# LB_BIT_i13_LIGHTSENSOR-v02_rev1.net
KiCad netlist of a schematic drawn in EAGLE
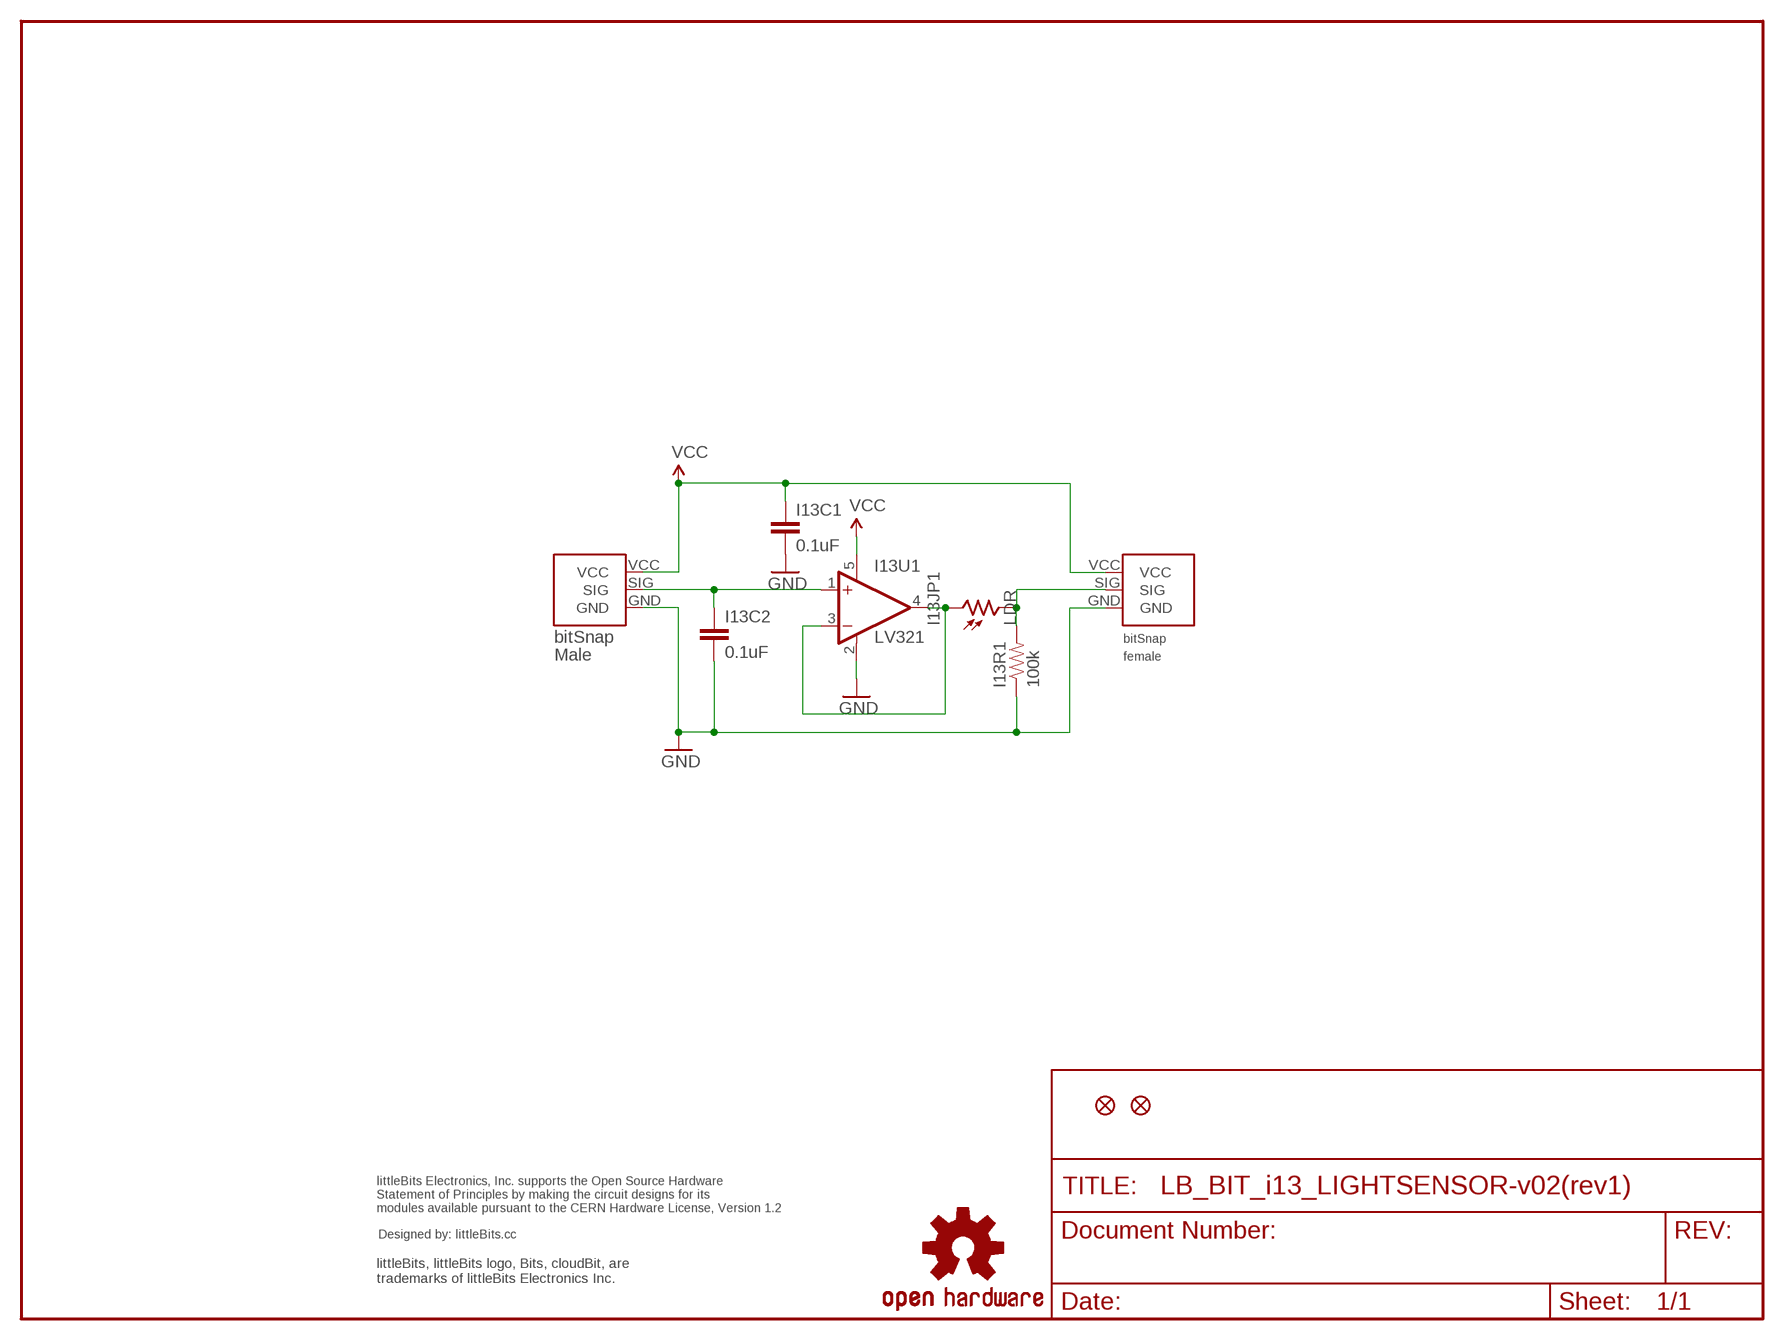
[diagram p0: schematic, sheet 1]

(export (version "E")
  (design (tool "Eeschema 10.0.6"))
  (components
    (comp (ref "I13BSF")
      (value "BITSNAP_FEMALE")
      (footprint "eagle-import:BITSNAP_FEMALE")
      (libsource (lib "eagle-import") (part "BITSNAP_FEMALE"))
    )
    (comp (ref "I13BSM")
      (value "BITSNAP_MALE")
      (footprint "eagle-import:BITSNAP_MALE")
      (libsource (lib "eagle-import") (part "BITSNAP_MALE"))
    )
    (comp (ref "I13C1")
      (value "0.1uF")
      (footprint "eagle-import:0603-CAP")
      (libsource (lib "eagle-import") (part "CAP0603-CAP"))
    )
    (comp (ref "I13C2")
      (value "0.1uF")
      (footprint "eagle-import:0603-CAP")
      (libsource (lib "eagle-import") (part "CAP0603-CAP"))
    )
    (comp (ref "I13FD1")
      (value "FIDUCIAL1X2")
      (footprint "eagle-import:FIDUCIAL-1X2")
      (libsource (lib "eagle-import") (part "FIDUCIAL1X2"))
    )
    (comp (ref "I13FD2")
      (value "FIDUCIAL1X2")
      (footprint "eagle-import:FIDUCIAL-1X2")
      (libsource (lib "eagle-import") (part "FIDUCIAL1X2"))
    )
    (comp (ref "I13JP1")
      (value "LDR")
      (footprint "eagle-import:T0-46-A10XX")
      (libsource (lib "eagle-import") (part "A1050_09"))
    )
    (comp (ref "I13R1")
      (value "100k")
      (footprint "eagle-import:0603-RES")
      (libsource (lib "eagle-import") (part "RESISTOR0603-RES"))
    )
    (comp (ref "I13U1")
      (value "LV321")
      (footprint "eagle-import:SC70-5")
      (libsource (lib "eagle-import") (part "LV321"))
    )
    (comp (ref "U$1")
      (value "OSHWCREDIT")
      (footprint "eagle-import:OSHWCREDIT")
      (libsource (lib "eagle-import") (part "OSHWCREDIT"))
    )
    (comp (ref "U$19")
      (value "OSHW-LOGOL")
      (footprint "eagle-import:OSHW-LOGO-L")
      (libsource (lib "eagle-import") (part "OSHW-LOGOL"))
    )
  )
  (nets
    (net (code "1") (name "GND") (class "Default")
      (node (ref "I13BSF") (pin "GND") (pinfunction "GND_GND") (pintype "bidirectional"))
      (node (ref "I13BSM") (pin "GND") (pinfunction "GND_GND") (pintype "bidirectional"))
      (node (ref "I13C1") (pin "2") (pinfunction "2_2") (pintype "passive"))
      (node (ref "I13C2") (pin "2") (pinfunction "2_2") (pintype "passive"))
      (node (ref "I13R1") (pin "1") (pinfunction "1_1") (pintype "passive"))
      (node (ref "I13U1") (pin "2") (pinfunction "V-_2") (pintype "power_in"))
    )
    (net (code "2") (name "Net-(I13BSF-PadSIG)") (class "Default")
      (node (ref "I13BSF") (pin "SIG") (pinfunction "SIG_SIG") (pintype "bidirectional"))
      (node (ref "I13JP1") (pin "2") (pinfunction "2_2") (pintype "passive"))
      (node (ref "I13R1") (pin "2") (pinfunction "2_2") (pintype "passive"))
    )
    (net (code "3") (name "Net-(I13U1-+IN)") (class "Default")
      (node (ref "I13BSM") (pin "SIG") (pinfunction "SIG_SIG") (pintype "bidirectional"))
      (node (ref "I13C2") (pin "1") (pinfunction "1_1") (pintype "passive"))
      (node (ref "I13U1") (pin "1") (pinfunction "+IN_1") (pintype "input"))
    )
    (net (code "4") (name "Net-(I13U1--IN)") (class "Default")
      (node (ref "I13JP1") (pin "1") (pinfunction "1_1") (pintype "passive"))
      (node (ref "I13U1") (pin "3") (pinfunction "-IN_3") (pintype "input"))
      (node (ref "I13U1") (pin "4") (pinfunction "OUT_4") (pintype "output"))
    )
    (net (code "5") (name "VCC") (class "Default")
      (node (ref "I13BSF") (pin "VCC") (pinfunction "VCC_VCC") (pintype "bidirectional"))
      (node (ref "I13BSM") (pin "VCC") (pinfunction "VCC_VCC") (pintype "bidirectional"))
      (node (ref "I13C1") (pin "1") (pinfunction "1_1") (pintype "passive"))
      (node (ref "I13U1") (pin "5") (pinfunction "V+_5") (pintype "power_in"))
    )
  )
)
